# 7segclock.net
KiCad netlist of a schematic drawn in EAGLE
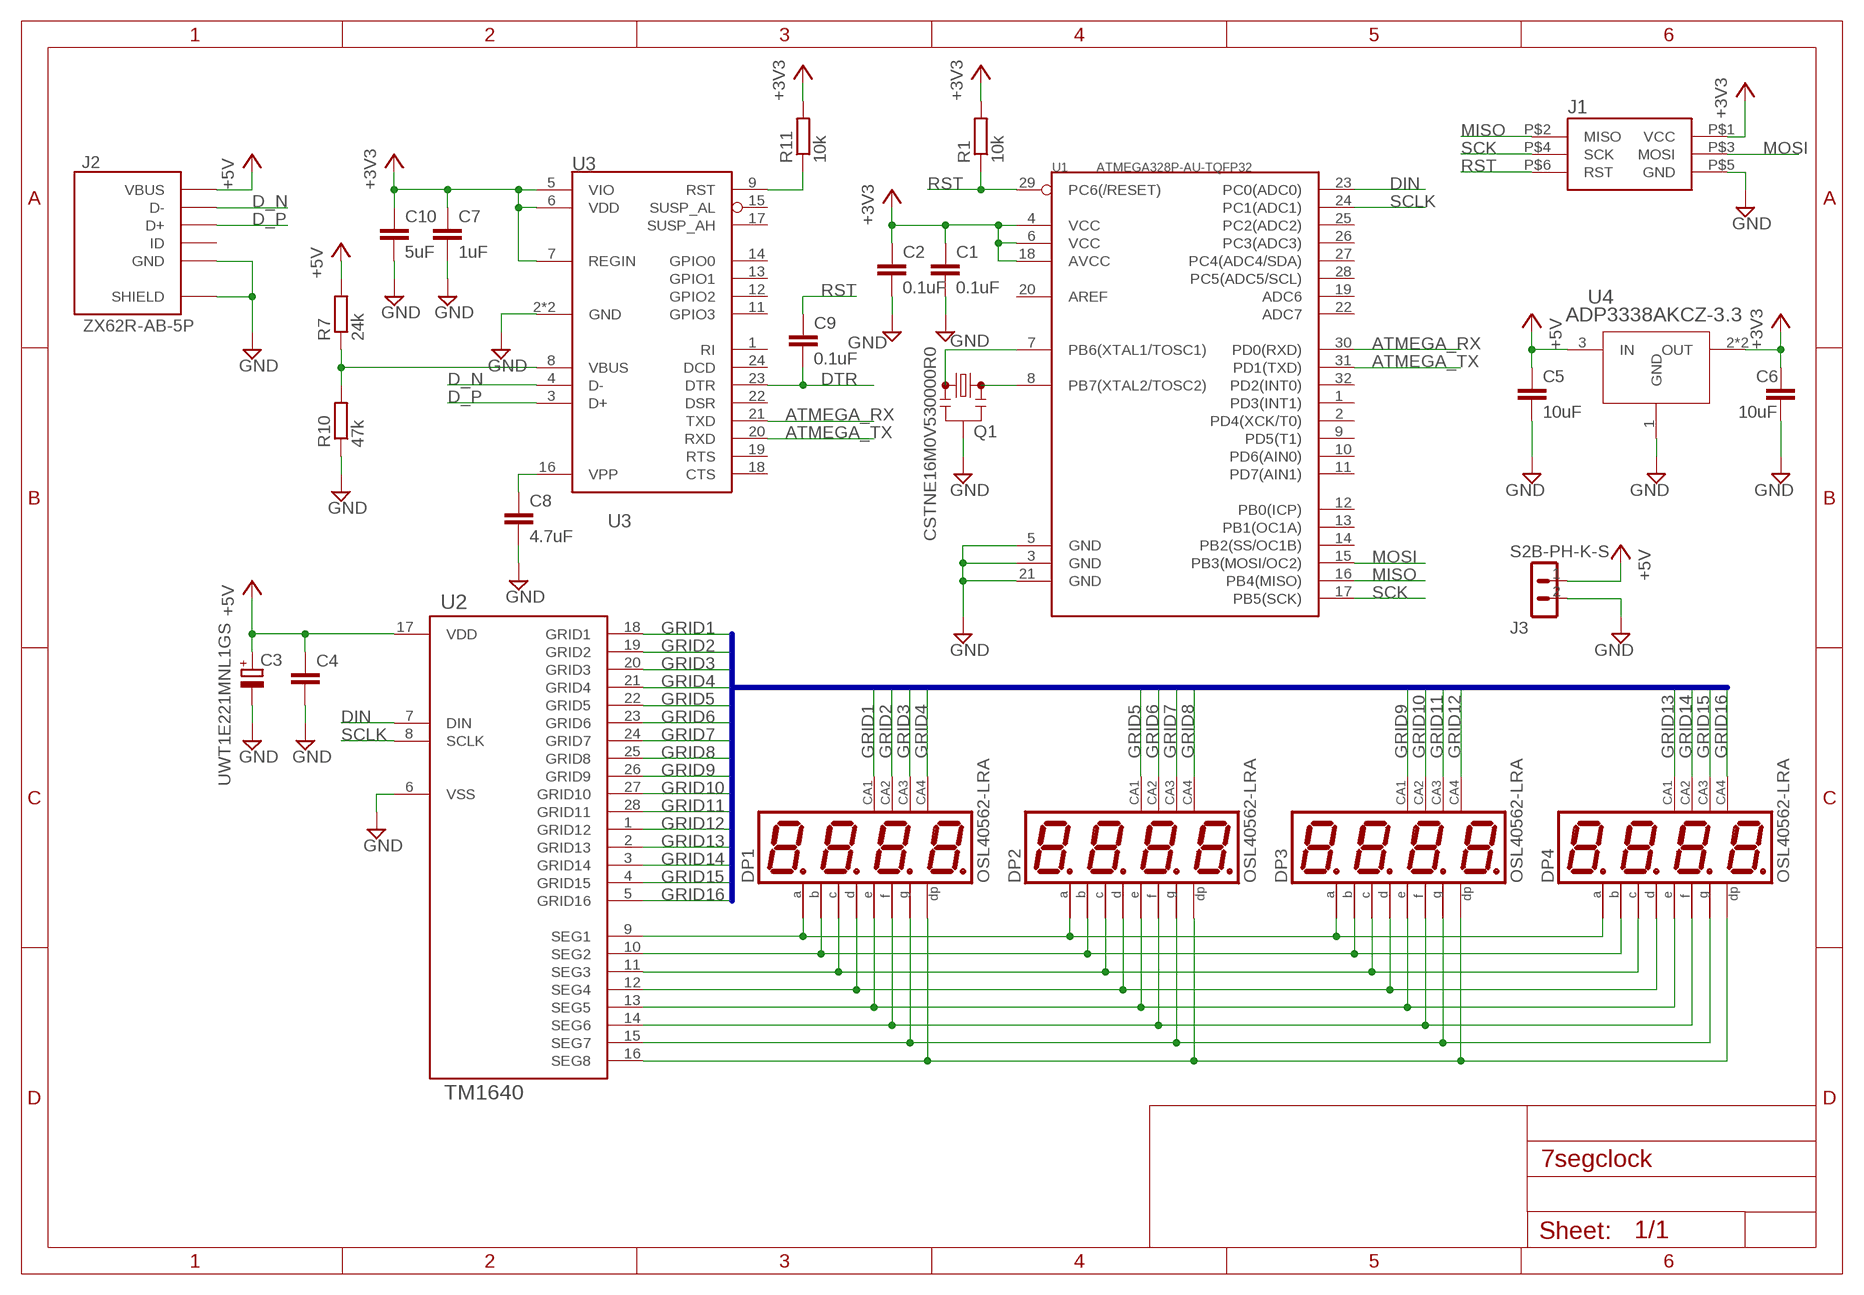
[diagram p0: schematic, sheet 1]

(export (version "E")
  (design (tool "Eeschema 10.0.6"))
  (components
    (comp (ref "C1")
      (value "0.1uF")
      (footprint "eagle-import:C0603")
      (libsource (lib "eagle-import") (part "C-EUC0603"))
    )
    (comp (ref "C2")
      (value "0.1uF")
      (footprint "eagle-import:C0603")
      (libsource (lib "eagle-import") (part "C-EUC0603"))
    )
    (comp (ref "C3")
      (value "UWT1E221MNL1GS")
      (footprint "eagle-import:NICHICON-ALMINUM-CAPACITOR-8MM")
      (libsource (lib "eagle-import") (part "UWT1E221MNL1GS"))
    )
    (comp (ref "C4")
      (value "C-EUC0603")
      (footprint "eagle-import:C0603")
      (libsource (lib "eagle-import") (part "C-EUC0603"))
    )
    (comp (ref "C5")
      (value "10uF")
      (footprint "eagle-import:C0603")
      (libsource (lib "eagle-import") (part "C-EUC0603"))
    )
    (comp (ref "C6")
      (value "10uF")
      (footprint "eagle-import:C0603")
      (libsource (lib "eagle-import") (part "C-EUC0603"))
    )
    (comp (ref "C7")
      (value "1uF")
      (footprint "eagle-import:C0603")
      (libsource (lib "eagle-import") (part "C-EUC0603"))
    )
    (comp (ref "C8")
      (value "4.7uF")
      (footprint "eagle-import:C0603")
      (libsource (lib "eagle-import") (part "C-EUC0603"))
    )
    (comp (ref "C9")
      (value "0.1uF")
      (footprint "eagle-import:C0603")
      (libsource (lib "eagle-import") (part "C-EUC0603"))
    )
    (comp (ref "C10")
      (value "5uF")
      (footprint "eagle-import:C0603")
      (libsource (lib "eagle-import") (part "C-EUC0603"))
    )
    (comp (ref "DP1")
      (value "OSL40562-LRA")
      (footprint "eagle-import:OSL40562-LRA")
      (libsource (lib "eagle-import") (part "OSL40562-LRA"))
    )
    (comp (ref "DP2")
      (value "OSL40562-LRA")
      (footprint "eagle-import:OSL40562-LRA")
      (libsource (lib "eagle-import") (part "OSL40562-LRA"))
    )
    (comp (ref "DP3")
      (value "OSL40562-LRA")
      (footprint "eagle-import:OSL40562-LRA")
      (libsource (lib "eagle-import") (part "OSL40562-LRA"))
    )
    (comp (ref "DP4")
      (value "OSL40562-LRA")
      (footprint "eagle-import:OSL40562-LRA")
      (libsource (lib "eagle-import") (part "OSL40562-LRA"))
    )
    (comp (ref "J1")
      (value "ICSP")
      (footprint "eagle-import:PIN_HEADER_MALE_2X03_06P")
      (libsource (lib "eagle-import") (part "ICSP"))
    )
    (comp (ref "J2")
      (value "ZX62R-AB-5P")
      (footprint "eagle-import:ZX62R-B-5PA")
      (libsource (lib "eagle-import") (part "ZX62R-AB-5P"))
    )
    (comp (ref "J3")
      (value "S2B-PH-K-S")
      (footprint "eagle-import:S2B-PH-K-S")
      (libsource (lib "eagle-import") (part "S2B-PH-K-S"))
    )
    (comp (ref "Q1")
      (value "CSTNE16M0V530000R0")
      (footprint "eagle-import:CSTNE16M0V530000R0")
      (libsource (lib "eagle-import") (part "CSTNE16M0V530000R0"))
    )
    (comp (ref "R1")
      (value "10k")
      (footprint "eagle-import:R0603")
      (libsource (lib "eagle-import") (part "R-EU_R0603"))
    )
    (comp (ref "R7")
      (value "24k")
      (footprint "eagle-import:R0603")
      (libsource (lib "eagle-import") (part "R-EU_R0603"))
    )
    (comp (ref "R10")
      (value "47k")
      (footprint "eagle-import:R0603")
      (libsource (lib "eagle-import") (part "R-EU_R0603"))
    )
    (comp (ref "R11")
      (value "10k")
      (footprint "eagle-import:R0603")
      (libsource (lib "eagle-import") (part "R-EU_R0603"))
    )
    (comp (ref "U1")
      (value "ATMEGA328P-AU-TQFP32")
      (footprint "eagle-import:TQFP32-0.8-7X7MM")
      (fields (field (name "MPN") "ATMEGA328P-AU"))
      (libsource (lib "eagle-import") (part "MCU-ATMEGA328P-AU(TQFP32)"))
    )
    (comp (ref "U2")
      (value "TM1640")
      (footprint "eagle-import:SOP28-TITANMICROELECTRONICS")
      (libsource (lib "eagle-import") (part "TM1640"))
    )
    (comp (ref "U3")
      (value "CP2104")
      (footprint "eagle-import:QFN24-SILABS")
      (libsource (lib "eagle-import") (part "CP2104"))
    )
    (comp (ref "U4")
      (value "ADP3338AKCZ-3.3")
      (footprint "eagle-import:SOT233")
      (libsource (lib "eagle-import") (part "ADP3338AKCZ-3.3"))
    )
  )
  (nets
    (net (code "1") (name "+3V3") (class "Default")
      (node (ref "C1") (pin "1") (pinfunction "1_1") (pintype "passive"))
      (node (ref "C10") (pin "1") (pinfunction "1_1") (pintype "passive"))
      (node (ref "C2") (pin "1") (pinfunction "1_1") (pintype "passive"))
      (node (ref "C6") (pin "1") (pinfunction "1_1") (pintype "passive"))
      (node (ref "C7") (pin "1") (pinfunction "1_1") (pintype "passive"))
      (node (ref "J1") (pin "P$1") (pinfunction "VCC_P$1") (pintype "bidirectional"))
      (node (ref "R1") (pin "2") (pinfunction "2_2") (pintype "passive"))
      (node (ref "R11") (pin "2") (pinfunction "2_2") (pintype "passive"))
      (node (ref "U1") (pin "18") (pinfunction "AVCC_18") (pintype "bidirectional"))
      (node (ref "U1") (pin "4") (pinfunction "VCC_4") (pintype "bidirectional"))
      (node (ref "U1") (pin "6") (pinfunction "VCC_6") (pintype "bidirectional"))
      (node (ref "U3") (pin "5") (pinfunction "VIO_5") (pintype "bidirectional"))
      (node (ref "U3") (pin "6") (pinfunction "VDD_6") (pintype "bidirectional"))
      (node (ref "U3") (pin "7") (pinfunction "REGIN_7") (pintype "bidirectional"))
      (node (ref "U4") (pin "2") (pinfunction "OUT_2") (pintype "passive"))
      (node (ref "U4") (pin "4") (pinfunction "OUT_4") (pintype "passive"))
    )
    (net (code "2") (name "+5V") (class "Default")
      (node (ref "C3") (pin "POS") (pinfunction "+_POS") (pintype "passive"))
      (node (ref "C4") (pin "1") (pinfunction "1_1") (pintype "passive"))
      (node (ref "C5") (pin "1") (pinfunction "1_1") (pintype "passive"))
      (node (ref "J2") (pin "VCC") (pinfunction "VBUS_VCC") (pintype "bidirectional"))
      (node (ref "J3") (pin "1") (pinfunction "1_1") (pintype "bidirectional"))
      (node (ref "R7") (pin "2") (pinfunction "2_2") (pintype "passive"))
      (node (ref "U2") (pin "17") (pinfunction "VDD_17") (pintype "bidirectional"))
      (node (ref "U4") (pin "3") (pinfunction "IN_3") (pintype "passive"))
    )
    (net (code "3") (name "/ATMEGA_RX") (class "Default")
      (node (ref "U1") (pin "30") (pinfunction "PD0(RXD)_30") (pintype "bidirectional"))
      (node (ref "U3") (pin "21") (pinfunction "TXD_21") (pintype "bidirectional"))
    )
    (net (code "4") (name "/ATMEGA_TX") (class "Default")
      (node (ref "U1") (pin "31") (pinfunction "PD1(TXD)_31") (pintype "bidirectional"))
      (node (ref "U3") (pin "20") (pinfunction "RXD_20") (pintype "bidirectional"))
    )
    (net (code "5") (name "/DIN") (class "Default")
      (node (ref "U1") (pin "23") (pinfunction "PC0(ADC0)_23") (pintype "bidirectional"))
      (node (ref "U2") (pin "7") (pinfunction "DIN_7") (pintype "bidirectional"))
    )
    (net (code "6") (name "/DTR") (class "Default")
      (node (ref "C9") (pin "2") (pinfunction "2_2") (pintype "passive"))
      (node (ref "U3") (pin "23") (pinfunction "DTR_23") (pintype "bidirectional"))
    )
    (net (code "7") (name "/D_N") (class "Default")
      (node (ref "J2") (pin "D-") (pinfunction "D-_D-") (pintype "bidirectional"))
      (node (ref "U3") (pin "4") (pinfunction "D-_4") (pintype "bidirectional"))
    )
    (net (code "8") (name "/D_P") (class "Default")
      (node (ref "J2") (pin "D+") (pinfunction "D+_D+") (pintype "bidirectional"))
      (node (ref "U3") (pin "3") (pinfunction "D+_3") (pintype "bidirectional"))
    )
    (net (code "9") (name "/GRID1") (class "Default")
      (node (ref "DP1") (pin "DIG1") (pinfunction "CA_DIG1") (pintype "passive"))
      (node (ref "U2") (pin "18") (pinfunction "GRID1_18") (pintype "bidirectional"))
    )
    (net (code "10") (name "/GRID2") (class "Default")
      (node (ref "DP1") (pin "DIG2") (pinfunction "CA_DIG2") (pintype "passive"))
      (node (ref "U2") (pin "19") (pinfunction "GRID2_19") (pintype "bidirectional"))
    )
    (net (code "11") (name "/GRID3") (class "Default")
      (node (ref "DP1") (pin "DIG3") (pinfunction "CA_DIG3") (pintype "passive"))
      (node (ref "U2") (pin "20") (pinfunction "GRID3_20") (pintype "bidirectional"))
    )
    (net (code "12") (name "/GRID4") (class "Default")
      (node (ref "DP1") (pin "DIG4") (pinfunction "CA_DIG4") (pintype "passive"))
      (node (ref "U2") (pin "21") (pinfunction "GRID4_21") (pintype "bidirectional"))
    )
    (net (code "13") (name "/GRID5") (class "Default")
      (node (ref "DP2") (pin "DIG1") (pinfunction "CA_DIG1") (pintype "passive"))
      (node (ref "U2") (pin "22") (pinfunction "GRID5_22") (pintype "bidirectional"))
    )
    (net (code "14") (name "/GRID6") (class "Default")
      (node (ref "DP2") (pin "DIG2") (pinfunction "CA_DIG2") (pintype "passive"))
      (node (ref "U2") (pin "23") (pinfunction "GRID6_23") (pintype "bidirectional"))
    )
    (net (code "15") (name "/GRID7") (class "Default")
      (node (ref "DP2") (pin "DIG3") (pinfunction "CA_DIG3") (pintype "passive"))
      (node (ref "U2") (pin "24") (pinfunction "GRID7_24") (pintype "bidirectional"))
    )
    (net (code "16") (name "/GRID8") (class "Default")
      (node (ref "DP2") (pin "DIG4") (pinfunction "CA_DIG4") (pintype "passive"))
      (node (ref "U2") (pin "25") (pinfunction "GRID8_25") (pintype "bidirectional"))
    )
    (net (code "17") (name "/GRID9") (class "Default")
      (node (ref "DP3") (pin "DIG1") (pinfunction "CA_DIG1") (pintype "passive"))
      (node (ref "U2") (pin "26") (pinfunction "GRID9_26") (pintype "bidirectional"))
    )
    (net (code "18") (name "/GRID10") (class "Default")
      (node (ref "DP3") (pin "DIG2") (pinfunction "CA_DIG2") (pintype "passive"))
      (node (ref "U2") (pin "27") (pinfunction "GRID10_27") (pintype "bidirectional"))
    )
    (net (code "19") (name "/GRID11") (class "Default")
      (node (ref "DP3") (pin "DIG3") (pinfunction "CA_DIG3") (pintype "passive"))
      (node (ref "U2") (pin "28") (pinfunction "GRID11_28") (pintype "bidirectional"))
    )
    (net (code "20") (name "/GRID12") (class "Default")
      (node (ref "DP3") (pin "DIG4") (pinfunction "CA_DIG4") (pintype "passive"))
      (node (ref "U2") (pin "1") (pinfunction "GRID12_1") (pintype "bidirectional"))
    )
    (net (code "21") (name "/GRID13") (class "Default")
      (node (ref "DP4") (pin "DIG1") (pinfunction "CA_DIG1") (pintype "passive"))
      (node (ref "U2") (pin "2") (pinfunction "GRID13_2") (pintype "bidirectional"))
    )
    (net (code "22") (name "/GRID14") (class "Default")
      (node (ref "DP4") (pin "DIG2") (pinfunction "CA_DIG2") (pintype "passive"))
      (node (ref "U2") (pin "3") (pinfunction "GRID14_3") (pintype "bidirectional"))
    )
    (net (code "23") (name "/GRID15") (class "Default")
      (node (ref "DP4") (pin "DIG3") (pinfunction "CA_DIG3") (pintype "passive"))
      (node (ref "U2") (pin "4") (pinfunction "GRID15_4") (pintype "bidirectional"))
    )
    (net (code "24") (name "/GRID16") (class "Default")
      (node (ref "DP4") (pin "DIG4") (pinfunction "CA_DIG4") (pintype "passive"))
      (node (ref "U2") (pin "5") (pinfunction "GRID16_5") (pintype "bidirectional"))
    )
    (net (code "25") (name "/MISO") (class "Default")
      (node (ref "J1") (pin "P$2") (pinfunction "MISO_P$2") (pintype "bidirectional"))
      (node (ref "U1") (pin "16") (pinfunction "PB4(MISO)_16") (pintype "bidirectional"))
    )
    (net (code "26") (name "/MOSI") (class "Default")
      (node (ref "J1") (pin "P$3") (pinfunction "MOSI_P$3") (pintype "bidirectional"))
      (node (ref "U1") (pin "15") (pinfunction "PB3(MOSI/OC2)_15") (pintype "bidirectional"))
    )
    (net (code "27") (name "/RST") (class "Default")
      (node (ref "C9") (pin "1") (pinfunction "1_1") (pintype "passive"))
      (node (ref "J1") (pin "P$6") (pinfunction "RST_P$6") (pintype "bidirectional"))
      (node (ref "R1") (pin "1") (pinfunction "1_1") (pintype "passive"))
      (node (ref "U1") (pin "29") (pinfunction "PC6(/RESET)_29") (pintype "bidirectional"))
    )
    (net (code "28") (name "/SCK") (class "Default")
      (node (ref "J1") (pin "P$4") (pinfunction "SCK_P$4") (pintype "bidirectional"))
      (node (ref "U1") (pin "17") (pinfunction "PB5(SCK)_17") (pintype "bidirectional"))
    )
    (net (code "29") (name "/SCLK") (class "Default")
      (node (ref "U1") (pin "24") (pinfunction "PC1(ADC1)_24") (pintype "bidirectional"))
      (node (ref "U2") (pin "8") (pinfunction "SCLK_8") (pintype "bidirectional"))
    )
    (net (code "30") (name "GND") (class "Default")
      (node (ref "C1") (pin "2") (pinfunction "2_2") (pintype "passive"))
      (node (ref "C10") (pin "2") (pinfunction "2_2") (pintype "passive"))
      (node (ref "C2") (pin "2") (pinfunction "2_2") (pintype "passive"))
      (node (ref "C3") (pin "NEG") (pinfunction "-_NEG") (pintype "passive"))
      (node (ref "C4") (pin "2") (pinfunction "2_2") (pintype "passive"))
      (node (ref "C5") (pin "2") (pinfunction "2_2") (pintype "passive"))
      (node (ref "C6") (pin "2") (pinfunction "2_2") (pintype "passive"))
      (node (ref "C7") (pin "2") (pinfunction "2_2") (pintype "passive"))
      (node (ref "C8") (pin "2") (pinfunction "2_2") (pintype "passive"))
      (node (ref "J1") (pin "P$5") (pinfunction "GND_P$5") (pintype "bidirectional"))
      (node (ref "J2") (pin "GND") (pinfunction "GND_GND") (pintype "bidirectional"))
      (node (ref "J2") (pin "SHIELD@1") (pinfunction "SHIELD_SHIELD@1") (pintype "bidirectional"))
      (node (ref "J2") (pin "SHIELD@2") (pinfunction "SHIELD_SHIELD@2") (pintype "bidirectional"))
      (node (ref "J2") (pin "SHIELD@3") (pinfunction "SHIELD_SHIELD@3") (pintype "bidirectional"))
      (node (ref "J2") (pin "SHIELD@4") (pinfunction "SHIELD_SHIELD@4") (pintype "bidirectional"))
      (node (ref "J3") (pin "2") (pinfunction "2_2") (pintype "bidirectional"))
      (node (ref "Q1") (pin "2") (pinfunction "2_2") (pintype "passive"))
      (node (ref "R10") (pin "1") (pinfunction "1_1") (pintype "passive"))
      (node (ref "U1") (pin "21") (pinfunction "GND_21") (pintype "bidirectional"))
      (node (ref "U1") (pin "3") (pinfunction "GND_3") (pintype "bidirectional"))
      (node (ref "U1") (pin "5") (pinfunction "GND_5") (pintype "bidirectional"))
      (node (ref "U2") (pin "6") (pinfunction "VSS_6") (pintype "bidirectional"))
      (node (ref "U3") (pin "2") (pinfunction "GND_2") (pintype "bidirectional"))
      (node (ref "U3") (pin "25") (pinfunction "GND_25") (pintype "bidirectional"))
      (node (ref "U4") (pin "1") (pinfunction "GND_1") (pintype "passive"))
    )
    (net (code "31") (name "Net-(U1-PB6(XTAL1{slash}TOSC1))") (class "Default")
      (node (ref "Q1") (pin "1") (pinfunction "1_1") (pintype "passive"))
      (node (ref "U1") (pin "7") (pinfunction "PB6(XTAL1/TOSC1)_7") (pintype "bidirectional"))
    )
    (net (code "32") (name "Net-(U1-PB7(XTAL2{slash}TOSC2))") (class "Default")
      (node (ref "Q1") (pin "3") (pinfunction "3_3") (pintype "passive"))
      (node (ref "U1") (pin "8") (pinfunction "PB7(XTAL2/TOSC2)_8") (pintype "bidirectional"))
    )
    (net (code "33") (name "Net-(U2-SEG1)") (class "Default")
      (node (ref "DP1") (pin "A") (pinfunction "A_A") (pintype "passive"))
      (node (ref "DP2") (pin "A") (pinfunction "A_A") (pintype "passive"))
      (node (ref "DP3") (pin "A") (pinfunction "A_A") (pintype "passive"))
      (node (ref "DP4") (pin "A") (pinfunction "A_A") (pintype "passive"))
      (node (ref "U2") (pin "9") (pinfunction "SEG1_9") (pintype "bidirectional"))
    )
    (net (code "34") (name "Net-(U2-SEG2)") (class "Default")
      (node (ref "DP1") (pin "B") (pinfunction "B_B") (pintype "passive"))
      (node (ref "DP2") (pin "B") (pinfunction "B_B") (pintype "passive"))
      (node (ref "DP3") (pin "B") (pinfunction "B_B") (pintype "passive"))
      (node (ref "DP4") (pin "B") (pinfunction "B_B") (pintype "passive"))
      (node (ref "U2") (pin "10") (pinfunction "SEG2_10") (pintype "bidirectional"))
    )
    (net (code "35") (name "Net-(U2-SEG3)") (class "Default")
      (node (ref "DP1") (pin "C") (pinfunction "C_C") (pintype "passive"))
      (node (ref "DP2") (pin "C") (pinfunction "C_C") (pintype "passive"))
      (node (ref "DP3") (pin "C") (pinfunction "C_C") (pintype "passive"))
      (node (ref "DP4") (pin "C") (pinfunction "C_C") (pintype "passive"))
      (node (ref "U2") (pin "11") (pinfunction "SEG3_11") (pintype "bidirectional"))
    )
    (net (code "36") (name "Net-(U2-SEG4)") (class "Default")
      (node (ref "DP1") (pin "D") (pinfunction "D_D") (pintype "passive"))
      (node (ref "DP2") (pin "D") (pinfunction "D_D") (pintype "passive"))
      (node (ref "DP3") (pin "D") (pinfunction "D_D") (pintype "passive"))
      (node (ref "DP4") (pin "D") (pinfunction "D_D") (pintype "passive"))
      (node (ref "U2") (pin "12") (pinfunction "SEG4_12") (pintype "bidirectional"))
    )
    (net (code "37") (name "Net-(U2-SEG5)") (class "Default")
      (node (ref "DP1") (pin "E") (pinfunction "E_E") (pintype "passive"))
      (node (ref "DP2") (pin "E") (pinfunction "E_E") (pintype "passive"))
      (node (ref "DP3") (pin "E") (pinfunction "E_E") (pintype "passive"))
      (node (ref "DP4") (pin "E") (pinfunction "E_E") (pintype "passive"))
      (node (ref "U2") (pin "13") (pinfunction "SEG5_13") (pintype "bidirectional"))
    )
    (net (code "38") (name "Net-(U2-SEG6)") (class "Default")
      (node (ref "DP1") (pin "F") (pinfunction "F_F") (pintype "passive"))
      (node (ref "DP2") (pin "F") (pinfunction "F_F") (pintype "passive"))
      (node (ref "DP3") (pin "F") (pinfunction "F_F") (pintype "passive"))
      (node (ref "DP4") (pin "F") (pinfunction "F_F") (pintype "passive"))
      (node (ref "U2") (pin "14") (pinfunction "SEG6_14") (pintype "bidirectional"))
    )
    (net (code "39") (name "Net-(U2-SEG7)") (class "Default")
      (node (ref "DP1") (pin "G") (pinfunction "G_G") (pintype "passive"))
      (node (ref "DP2") (pin "G") (pinfunction "G_G") (pintype "passive"))
      (node (ref "DP3") (pin "G") (pinfunction "G_G") (pintype "passive"))
      (node (ref "DP4") (pin "G") (pinfunction "G_G") (pintype "passive"))
      (node (ref "U2") (pin "15") (pinfunction "SEG7_15") (pintype "bidirectional"))
    )
    (net (code "40") (name "Net-(U2-SEG8)") (class "Default")
      (node (ref "DP1") (pin "DP") (pinfunction "DP_DP") (pintype "passive"))
      (node (ref "DP2") (pin "DP") (pinfunction "DP_DP") (pintype "passive"))
      (node (ref "DP3") (pin "DP") (pinfunction "DP_DP") (pintype "passive"))
      (node (ref "DP4") (pin "DP") (pinfunction "DP_DP") (pintype "passive"))
      (node (ref "U2") (pin "16") (pinfunction "SEG8_16") (pintype "bidirectional"))
    )
    (net (code "41") (name "Net-(U3-RST)") (class "Default")
      (node (ref "R11") (pin "1") (pinfunction "1_1") (pintype "passive"))
      (node (ref "U3") (pin "9") (pinfunction "RST_9") (pintype "bidirectional"))
    )
    (net (code "42") (name "Net-(U3-VBUS)") (class "Default")
      (node (ref "R10") (pin "2") (pinfunction "2_2") (pintype "passive"))
      (node (ref "R7") (pin "1") (pinfunction "1_1") (pintype "passive"))
      (node (ref "U3") (pin "8") (pinfunction "VBUS_8") (pintype "bidirectional"))
    )
    (net (code "43") (name "Net-(U3-VPP)") (class "Default")
      (node (ref "C8") (pin "1") (pinfunction "1_1") (pintype "passive"))
      (node (ref "U3") (pin "16") (pinfunction "VPP_16") (pintype "bidirectional"))
    )
    (net (code "44") (name "unconnected-(J2-PadID)") (class "Default")
      (node (ref "J2") (pin "ID") (pinfunction "ID_ID") (pintype "bidirectional"))
    )
    (net (code "45") (name "unconnected-(U1-ADC6-Pad19)") (class "Default")
      (node (ref "U1") (pin "19") (pinfunction "ADC6_19") (pintype "bidirectional"))
    )
    (net (code "46") (name "unconnected-(U1-ADC7-Pad22)") (class "Default")
      (node (ref "U1") (pin "22") (pinfunction "ADC7_22") (pintype "bidirectional"))
    )
    (net (code "47") (name "unconnected-(U1-AREF-Pad20)") (class "Default")
      (node (ref "U1") (pin "20") (pinfunction "AREF_20") (pintype "bidirectional"))
    )
    (net (code "48") (name "unconnected-(U1-PB0(ICP)-Pad12)") (class "Default")
      (node (ref "U1") (pin "12") (pinfunction "PB0(ICP)_12") (pintype "bidirectional"))
    )
    (net (code "49") (name "unconnected-(U1-PB1(OC1A)-Pad13)") (class "Default")
      (node (ref "U1") (pin "13") (pinfunction "PB1(OC1A)_13") (pintype "bidirectional"))
    )
    (net (code "50") (name "unconnected-(U1-PB2(SS{slash}OC1B)-Pad14)") (class "Default")
      (node (ref "U1") (pin "14") (pinfunction "PB2(SS/OC1B)_14") (pintype "bidirectional"))
    )
    (net (code "51") (name "unconnected-(U1-PC2(ADC2)-Pad25)") (class "Default")
      (node (ref "U1") (pin "25") (pinfunction "PC2(ADC2)_25") (pintype "bidirectional"))
    )
    (net (code "52") (name "unconnected-(U1-PC3(ADC3)-Pad26)") (class "Default")
      (node (ref "U1") (pin "26") (pinfunction "PC3(ADC3)_26") (pintype "bidirectional"))
    )
    (net (code "53") (name "unconnected-(U1-PC4(ADC4{slash}SDA)-Pad27)") (class "Default")
      (node (ref "U1") (pin "27") (pinfunction "PC4(ADC4/SDA)_27") (pintype "bidirectional"))
    )
    (net (code "54") (name "unconnected-(U1-PC5(ADC5{slash}SCL)-Pad28)") (class "Default")
      (node (ref "U1") (pin "28") (pinfunction "PC5(ADC5/SCL)_28") (pintype "bidirectional"))
    )
    (net (code "55") (name "unconnected-(U1-PD2(INT0)-Pad32)") (class "Default")
      (node (ref "U1") (pin "32") (pinfunction "PD2(INT0)_32") (pintype "bidirectional"))
    )
    (net (code "56") (name "unconnected-(U1-PD3(INT1)-Pad1)") (class "Default")
      (node (ref "U1") (pin "1") (pinfunction "PD3(INT1)_1") (pintype "bidirectional"))
    )
    (net (code "57") (name "unconnected-(U1-PD4(XCK{slash}T0)-Pad2)") (class "Default")
      (node (ref "U1") (pin "2") (pinfunction "PD4(XCK/T0)_2") (pintype "bidirectional"))
    )
    (net (code "58") (name "unconnected-(U1-PD5(T1)-Pad9)") (class "Default")
      (node (ref "U1") (pin "9") (pinfunction "PD5(T1)_9") (pintype "bidirectional"))
    )
    (net (code "59") (name "unconnected-(U1-PD6(AIN0)-Pad10)") (class "Default")
      (node (ref "U1") (pin "10") (pinfunction "PD6(AIN0)_10") (pintype "bidirectional"))
    )
    (net (code "60") (name "unconnected-(U1-PD7(AIN1)-Pad11)") (class "Default")
      (node (ref "U1") (pin "11") (pinfunction "PD7(AIN1)_11") (pintype "bidirectional"))
    )
    (net (code "61") (name "unconnected-(U3-CTS-Pad18)") (class "Default")
      (node (ref "U3") (pin "18") (pinfunction "CTS_18") (pintype "bidirectional"))
    )
    (net (code "62") (name "unconnected-(U3-DCD-Pad24)") (class "Default")
      (node (ref "U3") (pin "24") (pinfunction "DCD_24") (pintype "bidirectional"))
    )
    (net (code "63") (name "unconnected-(U3-DSR-Pad22)") (class "Default")
      (node (ref "U3") (pin "22") (pinfunction "DSR_22") (pintype "bidirectional"))
    )
    (net (code "64") (name "unconnected-(U3-GPIO0-Pad14)") (class "Default")
      (node (ref "U3") (pin "14") (pinfunction "GPIO0_14") (pintype "bidirectional"))
    )
    (net (code "65") (name "unconnected-(U3-GPIO1-Pad13)") (class "Default")
      (node (ref "U3") (pin "13") (pinfunction "GPIO1_13") (pintype "bidirectional"))
    )
    (net (code "66") (name "unconnected-(U3-GPIO2-Pad12)") (class "Default")
      (node (ref "U3") (pin "12") (pinfunction "GPIO2_12") (pintype "bidirectional"))
    )
    (net (code "67") (name "unconnected-(U3-GPIO3-Pad11)") (class "Default")
      (node (ref "U3") (pin "11") (pinfunction "GPIO3_11") (pintype "bidirectional"))
    )
    (net (code "68") (name "unconnected-(U3-RI-Pad1)") (class "Default")
      (node (ref "U3") (pin "1") (pinfunction "RI_1") (pintype "bidirectional"))
    )
    (net (code "69") (name "unconnected-(U3-RTS-Pad19)") (class "Default")
      (node (ref "U3") (pin "19") (pinfunction "RTS_19") (pintype "bidirectional"))
    )
    (net (code "70") (name "unconnected-(U3-SUSP_AH-Pad17)") (class "Default")
      (node (ref "U3") (pin "17") (pinfunction "SUSP_AH_17") (pintype "output"))
    )
    (net (code "71") (name "unconnected-(U3-SUSP_AL-Pad15)") (class "Default")
      (node (ref "U3") (pin "15") (pinfunction "SUSP_AL_15") (pintype "bidirectional"))
    )
  )
)
